# V1_2.net
KiCad netlist of a schematic drawn in Altium Designer
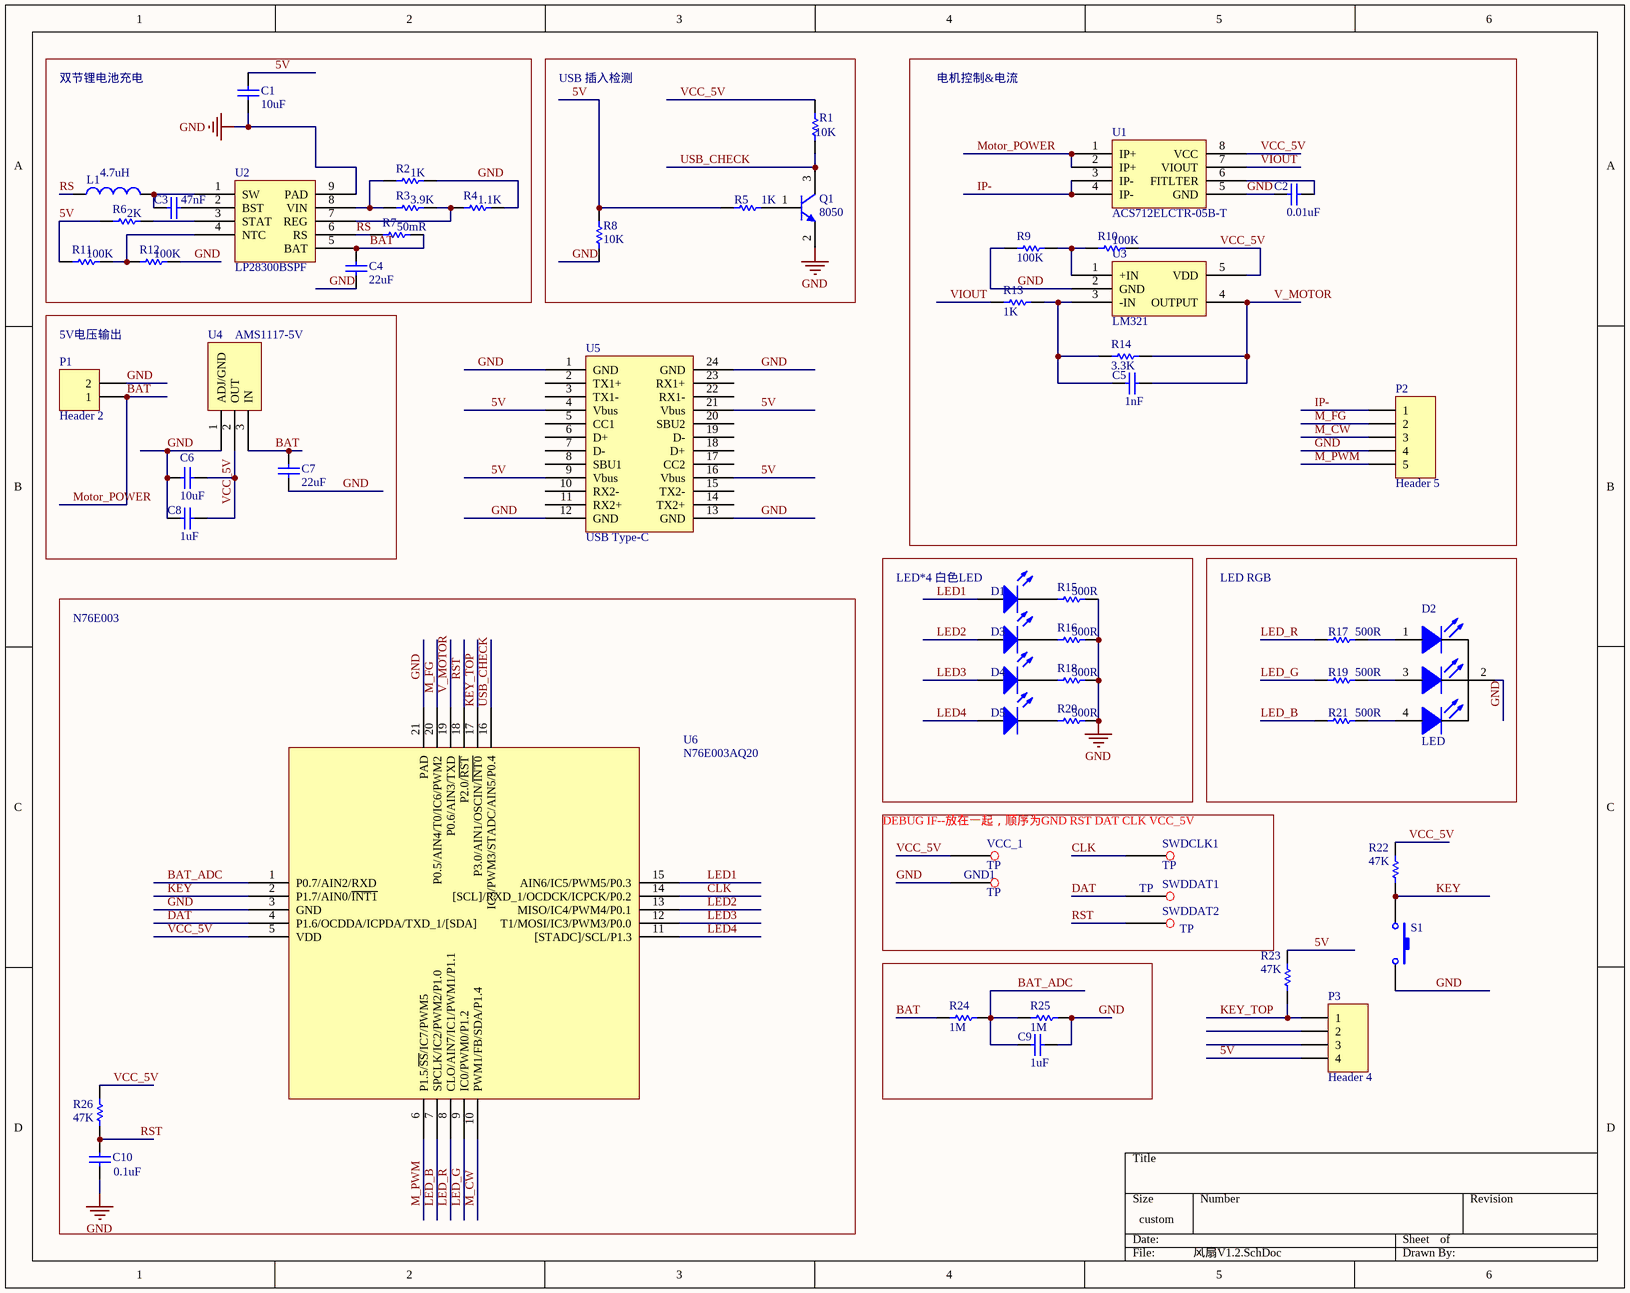
[diagram p0: 风扇V1.2.SchDoc]

(export (version "E")
  (design (tool "Eeschema 10.0.6"))
  (components
    (comp (ref "C1")
      (value "10uF")
      (footprint "c-0402")
      (description "Capacitor")
      (fields (field (name "Comment") "Cap") (field (name "PUBLISHER") "Altium Limited"))
      (libsource (lib "Miscellaneous Devices") (part "Cap"))
    )
    (comp (ref "C2")
      (value "0.01uF")
      (footprint "c-0402")
      (description "Capacitor")
      (fields (field (name "Comment") "Cap") (field (name "PUBLISHER") "Altium Limited"))
      (libsource (lib "Miscellaneous Devices") (part "Cap"))
    )
    (comp (ref "C3")
      (value "47nF")
      (footprint "c-0402")
      (description "Capacitor")
      (fields (field (name "Comment") "Cap") (field (name "PUBLISHER") "Altium Limited"))
      (libsource (lib "Miscellaneous Devices") (part "Cap"))
    )
    (comp (ref "C4")
      (value "22uF")
      (footprint "c-0402")
      (description "Capacitor")
      (fields (field (name "Comment") "Cap") (field (name "PUBLISHER") "Altium Limited"))
      (libsource (lib "Miscellaneous Devices") (part "Cap"))
    )
    (comp (ref "C5")
      (value "1nF")
      (footprint "c-0402")
      (description "Capacitor")
      (fields (field (name "Comment") "Cap") (field (name "PUBLISHER") "Altium Limited"))
      (libsource (lib "Miscellaneous Devices") (part "Cap"))
    )
    (comp (ref "C6")
      (value "10uF")
      (footprint "c-0402")
      (description "Capacitor")
      (fields (field (name "Comment") "Cap") (field (name "PUBLISHER") "Altium Limited"))
      (libsource (lib "Miscellaneous Devices") (part "Cap"))
    )
    (comp (ref "C7")
      (value "22uF")
      (footprint "c-0402")
      (description "Capacitor")
      (fields (field (name "Comment") "Cap") (field (name "PUBLISHER") "Altium Limited"))
      (libsource (lib "Miscellaneous Devices") (part "Cap"))
    )
    (comp (ref "C8")
      (value "1uF")
      (footprint "c-0402")
      (description "Capacitor")
      (fields (field (name "Comment") "Cap") (field (name "PUBLISHER") "Altium Limited"))
      (libsource (lib "Miscellaneous Devices") (part "Cap"))
    )
    (comp (ref "C9")
      (value "1uF")
      (footprint "c-0402")
      (description "Capacitor")
      (fields (field (name "Comment") "Cap") (field (name "PUBLISHER") "Altium Limited"))
      (libsource (lib "Miscellaneous Devices") (part "Cap"))
    )
    (comp (ref "C10")
      (value "0.1uF")
      (footprint "C-0402")
      (description "Capacitor")
      (fields (field (name "PUBLISHER") "Altium Limited"))
      (libsource (lib "Miscellaneous Devices") (part "Cap"))
    )
    (comp (ref "D1")
      (value "LED0")
      (footprint "Model Name")
      (description "Typical INFRARED GaAs LED")
      (fields (field (name "PUBLISHER") "Altium Limited"))
      (libsource (lib "Miscellaneous Devices") (part "LED0"))
    )
    (comp (ref "D2") (value "LED") (libsource (lib "SA2") (part "LED")))
    (comp (ref "D3")
      (value "LED0")
      (footprint "LED-0")
      (description "Typical INFRARED GaAs LED")
      (fields (field (name "PUBLISHER") "Altium Limited"))
      (libsource (lib "Miscellaneous Devices") (part "LED0"))
    )
    (comp (ref "D4")
      (value "LED0")
      (footprint "LED-0")
      (description "Typical INFRARED GaAs LED")
      (fields (field (name "PUBLISHER") "Altium Limited"))
      (libsource (lib "Miscellaneous Devices") (part "LED0"))
    )
    (comp (ref "D5")
      (value "LED0")
      (footprint "LED-0")
      (description "Typical INFRARED GaAs LED")
      (fields (field (name "PUBLISHER") "Altium Limited"))
      (libsource (lib "Miscellaneous Devices") (part "LED0"))
    )
    (comp (ref "GND1") (value "TP") (footprint "TP-1.2") (libsource (lib "Others_IC_SCH_LIB") (part "TP")))
    (comp (ref "L1")
      (value "4.7uH")
      (footprint "INDC1005AL")
      (description "Inductor")
      (fields (field (name "PUBLISHER") "Altium Limited"))
      (libsource (lib "Miscellaneous Devices") (part "Inductor"))
    )
    (comp (ref "P1")
      (value "Header 2")
      (footprint "HDR1X2")
      (description "Header, 2-Pin")
      (fields (field (name "PUBLISHER") "Altium Limited"))
      (libsource (lib "Miscellaneous Connectors") (part "Header 2"))
    )
    (comp (ref "P2")
      (value "Header 5")
      (footprint "HDR1X5")
      (description "Header, 5-Pin")
      (fields (field (name "PUBLISHER") "Altium Limited"))
      (libsource (lib "Miscellaneous Connectors") (part "Header 5"))
    )
    (comp (ref "P3")
      (value "Header 4")
      (footprint "HDR1X4")
      (description "Header, 4-Pin")
      (fields (field (name "PUBLISHER") "Altium Limited"))
      (libsource (lib "Miscellaneous Connectors") (part "Header 4"))
    )
    (comp (ref "Q1")
      (value "8050")
      (footprint "SOT-23")
      (description "NPN Bipolar Transistor")
      (fields (field (name "PUBLISHER") "Altium Limited"))
      (libsource (lib "Miscellaneous Devices") (part "NPN"))
    )
    (comp (ref "R1")
      (value "10K")
      (footprint "R-0402")
      (description "Resistor")
      (fields (field (name "PUBLISHER") "Altium Limited"))
      (libsource (lib "Miscellaneous Devices") (part "Res1"))
    )
    (comp (ref "R2")
      (value "1K")
      (footprint "R-0402")
      (description "Resistor")
      (fields (field (name "Comment") "Res1") (field (name "PUBLISHER") "Altium Limited"))
      (libsource (lib "Miscellaneous Devices") (part "Res1"))
    )
    (comp (ref "R3")
      (value "3.9K")
      (footprint "R-0402")
      (description "Resistor")
      (fields (field (name "Comment") "Res1") (field (name "PUBLISHER") "Altium Limited"))
      (libsource (lib "Miscellaneous Devices") (part "Res1"))
    )
    (comp (ref "R4")
      (value "1.1K")
      (footprint "R-0402")
      (description "Resistor")
      (fields (field (name "Comment") "Res1") (field (name "PUBLISHER") "Altium Limited"))
      (libsource (lib "Miscellaneous Devices") (part "Res1"))
    )
    (comp (ref "R5")
      (value "1K")
      (footprint "R-0402")
      (description "Resistor")
      (fields (field (name "PUBLISHER") "Altium Limited"))
      (libsource (lib "Miscellaneous Devices") (part "Res1"))
    )
    (comp (ref "R6")
      (value "2K")
      (footprint "R-0402")
      (description "Resistor")
      (fields (field (name "Comment") "Res1") (field (name "PUBLISHER") "Altium Limited"))
      (libsource (lib "Miscellaneous Devices") (part "Res1"))
    )
    (comp (ref "R7")
      (value "50mR")
      (footprint "R-0402")
      (description "Resistor")
      (fields (field (name "Comment") "Res1") (field (name "PUBLISHER") "Altium Limited"))
      (libsource (lib "Miscellaneous Devices") (part "Res1"))
    )
    (comp (ref "R8")
      (value "10K")
      (footprint "R-0402")
      (description "Resistor")
      (fields (field (name "Comment") "Res1") (field (name "PUBLISHER") "Altium Limited"))
      (libsource (lib "Miscellaneous Devices") (part "Res1"))
    )
    (comp (ref "R9")
      (value "100K")
      (footprint "R-0402")
      (description "Resistor")
      (fields (field (name "Comment") "Res1") (field (name "PUBLISHER") "Altium Limited"))
      (libsource (lib "Miscellaneous Devices") (part "Res1"))
    )
    (comp (ref "R10")
      (value "100K")
      (footprint "R-0402")
      (description "Resistor")
      (fields (field (name "Comment") "Res1") (field (name "PUBLISHER") "Altium Limited"))
      (libsource (lib "Miscellaneous Devices") (part "Res1"))
    )
    (comp (ref "R11")
      (value "100K")
      (footprint "R-0402")
      (description "Resistor")
      (fields (field (name "Comment") "Res1") (field (name "PUBLISHER") "Altium Limited"))
      (libsource (lib "Miscellaneous Devices") (part "Res1"))
    )
    (comp (ref "R12")
      (value "100K")
      (footprint "R-0402")
      (description "Resistor")
      (fields (field (name "Comment") "Res1") (field (name "PUBLISHER") "Altium Limited"))
      (libsource (lib "Miscellaneous Devices") (part "Res1"))
    )
    (comp (ref "R13")
      (value "1K")
      (footprint "R-0402")
      (description "Resistor")
      (fields (field (name "Comment") "Res1") (field (name "PUBLISHER") "Altium Limited"))
      (libsource (lib "Miscellaneous Devices") (part "Res1"))
    )
    (comp (ref "R14")
      (value "3.3K")
      (footprint "R-0402")
      (description "Resistor")
      (fields (field (name "Comment") "Res1") (field (name "PUBLISHER") "Altium Limited"))
      (libsource (lib "Miscellaneous Devices") (part "Res1"))
    )
    (comp (ref "R15")
      (value "500R")
      (footprint "R-0402")
      (description "Resistor")
      (fields (field (name "Comment") "Res1") (field (name "PUBLISHER") "Altium Limited"))
      (libsource (lib "Miscellaneous Devices") (part "Res1"))
    )
    (comp (ref "R16")
      (value "500R")
      (footprint "R-0402")
      (description "Resistor")
      (fields (field (name "Comment") "Res1") (field (name "PUBLISHER") "Altium Limited"))
      (libsource (lib "Miscellaneous Devices") (part "Res1"))
    )
    (comp (ref "R17")
      (value "500R")
      (footprint "R-0402")
      (description "Resistor")
      (fields (field (name "PUBLISHER") "Altium Limited"))
      (libsource (lib "Miscellaneous Devices") (part "Res1"))
    )
    (comp (ref "R18")
      (value "500R")
      (footprint "R-0402")
      (description "Resistor")
      (fields (field (name "Comment") "Res1") (field (name "PUBLISHER") "Altium Limited"))
      (libsource (lib "Miscellaneous Devices") (part "Res1"))
    )
    (comp (ref "R19")
      (value "500R")
      (footprint "R-0402")
      (description "Resistor")
      (fields (field (name "PUBLISHER") "Altium Limited"))
      (libsource (lib "Miscellaneous Devices") (part "Res1"))
    )
    (comp (ref "R20")
      (value "500R")
      (footprint "R-0402")
      (description "Resistor")
      (fields (field (name "Comment") "Res1") (field (name "PUBLISHER") "Altium Limited"))
      (libsource (lib "Miscellaneous Devices") (part "Res1"))
    )
    (comp (ref "R21")
      (value "500R")
      (footprint "R-0402")
      (description "Resistor")
      (fields (field (name "PUBLISHER") "Altium Limited"))
      (libsource (lib "Miscellaneous Devices") (part "Res1"))
    )
    (comp (ref "R22")
      (value "47K")
      (footprint "r-0201")
      (description "Resistor")
      (fields (field (name "Comment") "Res1") (field (name "PUBLISHER") "Altium Limited"))
      (libsource (lib "Miscellaneous Devices") (part "Res1"))
    )
    (comp (ref "R23")
      (value "47K")
      (footprint "r-0201")
      (description "Resistor")
      (fields (field (name "Comment") "Res1") (field (name "PUBLISHER") "Altium Limited"))
      (libsource (lib "Miscellaneous Devices") (part "Res1"))
    )
    (comp (ref "R24")
      (value "1M")
      (footprint "R-0402")
      (description "Resistor")
      (fields (field (name "Comment") "Res1") (field (name "PUBLISHER") "Altium Limited"))
      (libsource (lib "Miscellaneous Devices") (part "Res1"))
    )
    (comp (ref "R25")
      (value "1M")
      (footprint "R-0402")
      (description "Resistor")
      (fields (field (name "Comment") "Res1") (field (name "PUBLISHER") "Altium Limited"))
      (libsource (lib "Miscellaneous Devices") (part "Res1"))
    )
    (comp (ref "R26")
      (value "47K")
      (footprint "R-0402")
      (description "Resistor")
      (fields (field (name "PUBLISHER") "Altium Limited"))
      (libsource (lib "Miscellaneous Devices") (part "Res1"))
    )
    (comp (ref "S1")
      (value "SW-PB")
      (footprint "SWITCH")
      (description "Switch")
      (fields (field (name "PUBLISHER") "Altium Limited"))
      (libsource (lib "Miscellaneous Devices") (part "SW-PB"))
    )
    (comp (ref "SWDCLK1") (value "TP") (footprint "TP-1.2") (libsource (lib "Others_IC_SCH_LIB") (part "TP")))
    (comp (ref "SWDDAT1") (value "TP") (footprint "TP-1.2") (libsource (lib "Others_IC_SCH_LIB") (part "TP")))
    (comp (ref "SWDDAT2") (value "TP") (footprint "TP-1.2") (libsource (lib "Others_IC_SCH_LIB") (part "TP")))
    (comp (ref "U1")
      (value "ACS712ELCTR-05B-T")
      (footprint "SOIC8")
      (libsource (lib "Others_IC_SCH_LIB") (part "ACS712ELCTR-05B-T"))
    )
    (comp (ref "U2")
      (value "LP28300BSPF")
      (footprint "ESOP8")
      (libsource (lib "Others_IC_SCH_LIB") (part "LP28300BSPF"))
    )
    (comp (ref "U3")
      (value "LM321")
      (footprint "SOT-23-5")
      (libsource (lib "Others_IC_SCH_LIB") (part "LM321"))
    )
    (comp (ref "U4") (value "AMS1117-5V") (libsource (lib "Others_IC_SCH_LIB") (part "AMS1117")))
    (comp (ref "U5") (value "USB Type-C") (libsource (lib "Others_IC_SCH_LIB") (part "USB Type-C")))
    (comp (ref "U6")
      (value "N76E003AQ20")
      (footprint "QFN-20 0.4mm")
      (libsource (lib "Others_IC_SCH_LIB") (part "N76E003AQ20"))
    )
    (comp (ref "VCC_1") (value "TP") (footprint "TP-1.2") (libsource (lib "Others_IC_SCH_LIB") (part "TP")))
  )
  (nets
    (net (code "1") (name "/5V") (class "Default")
      (node (ref "C1") (pin "1") (pinfunction "1_1") (pintype "passive"))
      (node (ref "P3") (pin "4") (pinfunction "4_4") (pintype "passive"))
      (node (ref "R11") (pin "2") (pinfunction "2_2") (pintype "passive"))
      (node (ref "R23") (pin "2") (pinfunction "2_2") (pintype "passive"))
      (node (ref "R5") (pin "1") (pinfunction "1_1") (pintype "passive"))
      (node (ref "R6") (pin "2") (pinfunction "2_2") (pintype "passive"))
      (node (ref "R8") (pin "1") (pinfunction "1_1") (pintype "passive"))
      (node (ref "U5") (pin "16") (pinfunction "Vbus_16") (pintype "passive"))
      (node (ref "U5") (pin "21") (pinfunction "Vbus_21") (pintype "passive"))
      (node (ref "U5") (pin "4") (pinfunction "Vbus_4") (pintype "passive"))
      (node (ref "U5") (pin "9") (pinfunction "Vbus_9") (pintype "passive"))
    )
    (net (code "2") (name "/BAT") (class "Default")
      (node (ref "C4") (pin "1") (pinfunction "1_1") (pintype "passive"))
      (node (ref "C7") (pin "2") (pinfunction "2_2") (pintype "passive"))
      (node (ref "P1") (pin "1") (pinfunction "1_1") (pintype "passive"))
      (node (ref "R24") (pin "1") (pinfunction "1_1") (pintype "passive"))
      (node (ref "R7") (pin "1") (pinfunction "1_1") (pintype "passive"))
      (node (ref "U1") (pin "1") (pinfunction "IP+_1") (pintype "passive"))
      (node (ref "U1") (pin "2") (pinfunction "IP+_2") (pintype "passive"))
      (node (ref "U2") (pin "5") (pinfunction "BAT_5") (pintype "passive"))
      (node (ref "U4") (pin "3") (pinfunction "IN_3") (pintype "passive"))
    )
    (net (code "3") (name "/BAT_ADC") (class "Default")
      (node (ref "C9") (pin "2") (pinfunction "2_2") (pintype "passive"))
      (node (ref "R24") (pin "2") (pinfunction "2_2") (pintype "passive"))
      (node (ref "R25") (pin "1") (pinfunction "1_1") (pintype "passive"))
      (node (ref "U6") (pin "1") (pinfunction "P0.7/AIN2/RXD_1") (pintype "passive"))
    )
    (net (code "4") (name "/CLK") (class "Default")
      (node (ref "SWDCLK1") (pin "1") (pinfunction "1_1") (pintype "passive"))
      (node (ref "U6") (pin "14") (pinfunction "[SCL]/RXD_1/OCDCK/ICPCK/P0.2_14") (pintype "passive"))
    )
    (net (code "5") (name "/DAT") (class "Default")
      (node (ref "SWDDAT1") (pin "1") (pinfunction "1_1") (pintype "passive"))
      (node (ref "U6") (pin "4") (pinfunction "P1.6/OCDDA/ICPDA/TXD_1/[SDA]_4") (pintype "passive"))
    )
    (net (code "6") (name "/IP-") (class "Default")
      (node (ref "P2") (pin "1") (pinfunction "1_1") (pintype "passive"))
      (node (ref "U1") (pin "3") (pinfunction "IP-_3") (pintype "passive"))
      (node (ref "U1") (pin "4") (pinfunction "IP-_4") (pintype "passive"))
    )
    (net (code "7") (name "/KEY") (class "Default")
      (node (ref "R22") (pin "1") (pinfunction "1_1") (pintype "passive"))
      (node (ref "S1") (pin "1") (pinfunction "1_1") (pintype "passive"))
      (node (ref "U6") (pin "2") (pinfunction "P1.7/AIN0/~{INT1}_2") (pintype "passive"))
    )
    (net (code "8") (name "/KEY_TOP") (class "Default")
      (node (ref "P3") (pin "1") (pinfunction "1_1") (pintype "passive"))
      (node (ref "R23") (pin "1") (pinfunction "1_1") (pintype "passive"))
      (node (ref "U6") (pin "17") (pinfunction "P3.0/AIN1/OSCIN/~{INT0}_17") (pintype "passive"))
    )
    (net (code "9") (name "/LED1") (class "Default")
      (node (ref "D1") (pin "1") (pinfunction "A_1") (pintype "passive"))
      (node (ref "U6") (pin "15") (pinfunction "AIN6/IC5/PWM5/P0.3_15") (pintype "passive"))
    )
    (net (code "10") (name "/LED2") (class "Default")
      (node (ref "D3") (pin "1") (pinfunction "A_1") (pintype "passive"))
      (node (ref "U6") (pin "13") (pinfunction "MISO/IC4/PWM4/P0.1_13") (pintype "passive"))
    )
    (net (code "11") (name "/LED3") (class "Default")
      (node (ref "D4") (pin "1") (pinfunction "A_1") (pintype "passive"))
      (node (ref "U6") (pin "12") (pinfunction "T1/MOSI/IC3/PWM3/P0.0_12") (pintype "passive"))
    )
    (net (code "12") (name "/LED4") (class "Default")
      (node (ref "D5") (pin "1") (pinfunction "A_1") (pintype "passive"))
      (node (ref "U6") (pin "11") (pinfunction "[STADC]/SCL/P1.3_11") (pintype "passive"))
    )
    (net (code "13") (name "/LED_B") (class "Default")
      (node (ref "R21") (pin "1") (pinfunction "1_1") (pintype "passive"))
      (node (ref "U6") (pin "7") (pinfunction "SPCLK/IC2/PWM2/P1.0_7") (pintype "passive"))
    )
    (net (code "14") (name "/LED_G") (class "Default")
      (node (ref "R19") (pin "1") (pinfunction "1_1") (pintype "passive"))
      (node (ref "U6") (pin "9") (pinfunction "IC0/PWM0/P1.2_9") (pintype "passive"))
    )
    (net (code "15") (name "/LED_R") (class "Default")
      (node (ref "R17") (pin "1") (pinfunction "1_1") (pintype "passive"))
      (node (ref "U6") (pin "8") (pinfunction "CLO/AIN7/IC1/PWM1/P1.1_8") (pintype "passive"))
    )
    (net (code "16") (name "/M_CW") (class "Default")
      (node (ref "P2") (pin "3") (pinfunction "3_3") (pintype "passive"))
      (node (ref "U6") (pin "10") (pinfunction "PWM1/FB/SDA/P1.4_10") (pintype "passive"))
    )
    (net (code "17") (name "/M_FG") (class "Default")
      (node (ref "P2") (pin "2") (pinfunction "2_2") (pintype "passive"))
      (node (ref "U6") (pin "20") (pinfunction "P0.5/AIN4/T0/IC6/PWM2_20") (pintype "passive"))
    )
    (net (code "18") (name "/M_PWM") (class "Default")
      (node (ref "P2") (pin "5") (pinfunction "5_5") (pintype "passive"))
      (node (ref "U6") (pin "6") (pinfunction "P1.5/~{SS}/IC7/PWM5_6") (pintype "passive"))
    )
    (net (code "19") (name "/RS") (class "Default")
      (node (ref "L1") (pin "1") (pinfunction "1_1") (pintype "passive"))
      (node (ref "R7") (pin "2") (pinfunction "2_2") (pintype "passive"))
      (node (ref "U2") (pin "6") (pinfunction "RS_6") (pintype "passive"))
    )
    (net (code "20") (name "/RST") (class "Default")
      (node (ref "C10") (pin "2") (pinfunction "2_2") (pintype "passive"))
      (node (ref "R26") (pin "1") (pinfunction "1_1") (pintype "passive"))
      (node (ref "SWDDAT2") (pin "1") (pinfunction "1_1") (pintype "passive"))
      (node (ref "U6") (pin "18") (pinfunction "P2.0/~{RST}_18") (pintype "passive"))
    )
    (net (code "21") (name "/USB_CHECK") (class "Default")
      (node (ref "Q1") (pin "3") (pinfunction "C_3") (pintype "passive"))
      (node (ref "R1") (pin "1") (pinfunction "1_1") (pintype "passive"))
      (node (ref "U6") (pin "16") (pinfunction "IC3/PWM3/STADC/AIN5/P0.4_16") (pintype "passive"))
    )
    (net (code "22") (name "/VCC_5V") (class "Default")
      (node (ref "C6") (pin "2") (pinfunction "2_2") (pintype "passive"))
      (node (ref "C8") (pin "2") (pinfunction "2_2") (pintype "passive"))
      (node (ref "R1") (pin "2") (pinfunction "2_2") (pintype "passive"))
      (node (ref "R10") (pin "2") (pinfunction "2_2") (pintype "passive"))
      (node (ref "R22") (pin "2") (pinfunction "2_2") (pintype "passive"))
      (node (ref "R26") (pin "2") (pinfunction "2_2") (pintype "passive"))
      (node (ref "U1") (pin "8") (pinfunction "VCC_8") (pintype "passive"))
      (node (ref "U3") (pin "5") (pinfunction "VDD_5") (pintype "passive"))
      (node (ref "U4") (pin "2") (pinfunction "OUT_2") (pintype "passive"))
      (node (ref "U6") (pin "5") (pinfunction "VDD_5") (pintype "passive"))
      (node (ref "VCC_1") (pin "1") (pinfunction "1_1") (pintype "passive"))
    )
    (net (code "23") (name "/VIOUT") (class "Default")
      (node (ref "R13") (pin "1") (pinfunction "1_1") (pintype "passive"))
      (node (ref "U1") (pin "7") (pinfunction "VIOUT_7") (pintype "passive"))
    )
    (net (code "24") (name "/V_MOTOR") (class "Default")
      (node (ref "C5") (pin "1") (pinfunction "1_1") (pintype "passive"))
      (node (ref "R14") (pin "2") (pinfunction "2_2") (pintype "passive"))
      (node (ref "U3") (pin "4") (pinfunction "OUTPUT_4") (pintype "passive"))
      (node (ref "U6") (pin "19") (pinfunction "P0.6/AIN3/TXD_19") (pintype "passive"))
    )
    (net (code "25") (name "GND") (class "Default")
      (node (ref "C1") (pin "2") (pinfunction "2_2") (pintype "passive"))
      (node (ref "C10") (pin "1") (pinfunction "1_1") (pintype "passive"))
      (node (ref "C2") (pin "2") (pinfunction "2_2") (pintype "passive"))
      (node (ref "C4") (pin "2") (pinfunction "2_2") (pintype "passive"))
      (node (ref "C6") (pin "1") (pinfunction "1_1") (pintype "passive"))
      (node (ref "C7") (pin "1") (pinfunction "1_1") (pintype "passive"))
      (node (ref "C8") (pin "1") (pinfunction "1_1") (pintype "passive"))
      (node (ref "C9") (pin "1") (pinfunction "1_1") (pintype "passive"))
      (node (ref "D2") (pin "2") (pinfunction "2_2") (pintype "passive"))
      (node (ref "GND1") (pin "1") (pinfunction "1_1") (pintype "passive"))
      (node (ref "P1") (pin "2") (pinfunction "2_2") (pintype "passive"))
      (node (ref "P2") (pin "4") (pinfunction "4_4") (pintype "passive"))
      (node (ref "Q1") (pin "2") (pinfunction "E_2") (pintype "passive"))
      (node (ref "R12") (pin "1") (pinfunction "1_1") (pintype "passive"))
      (node (ref "R15") (pin "2") (pinfunction "2_2") (pintype "passive"))
      (node (ref "R16") (pin "2") (pinfunction "2_2") (pintype "passive"))
      (node (ref "R18") (pin "2") (pinfunction "2_2") (pintype "passive"))
      (node (ref "R2") (pin "1") (pinfunction "1_1") (pintype "passive"))
      (node (ref "R20") (pin "2") (pinfunction "2_2") (pintype "passive"))
      (node (ref "R25") (pin "2") (pinfunction "2_2") (pintype "passive"))
      (node (ref "R4") (pin "1") (pinfunction "1_1") (pintype "passive"))
      (node (ref "R8") (pin "2") (pinfunction "2_2") (pintype "passive"))
      (node (ref "R9") (pin "1") (pinfunction "1_1") (pintype "passive"))
      (node (ref "S1") (pin "2") (pinfunction "2_2") (pintype "passive"))
      (node (ref "U1") (pin "5") (pinfunction "GND_5") (pintype "passive"))
      (node (ref "U2") (pin "9") (pinfunction "PAD_9") (pintype "passive"))
      (node (ref "U3") (pin "2") (pinfunction "GND_2") (pintype "passive"))
      (node (ref "U4") (pin "1") (pinfunction "ADJ/GND_1") (pintype "passive"))
      (node (ref "U5") (pin "1") (pinfunction "GND_1") (pintype "passive"))
      (node (ref "U5") (pin "12") (pinfunction "GND_12") (pintype "passive"))
      (node (ref "U5") (pin "13") (pinfunction "GND_13") (pintype "passive"))
      (node (ref "U5") (pin "24") (pinfunction "GND_24") (pintype "passive"))
      (node (ref "U6") (pin "21") (pinfunction "PAD_21") (pintype "passive"))
      (node (ref "U6") (pin "3") (pinfunction "GND_3") (pintype "passive"))
    )
    (net (code "26") (name "Net-(D1-K)") (class "Default")
      (node (ref "D1") (pin "2") (pinfunction "K_2") (pintype "passive"))
      (node (ref "R15") (pin "1") (pinfunction "1_1") (pintype "passive"))
    )
    (net (code "27") (name "Net-(D2-Pad1)") (class "Default")
      (node (ref "D2") (pin "1") (pinfunction "1_1") (pintype "passive"))
      (node (ref "R17") (pin "2") (pinfunction "2_2") (pintype "passive"))
    )
    (net (code "28") (name "Net-(D2-Pad3)") (class "Default")
      (node (ref "D2") (pin "3") (pinfunction "3_3") (pintype "passive"))
      (node (ref "R19") (pin "2") (pinfunction "2_2") (pintype "passive"))
    )
    (net (code "29") (name "Net-(D2-Pad4)") (class "Default")
      (node (ref "D2") (pin "4") (pinfunction "4_4") (pintype "passive"))
      (node (ref "R21") (pin "2") (pinfunction "2_2") (pintype "passive"))
    )
    (net (code "30") (name "Net-(D3-K)") (class "Default")
      (node (ref "D3") (pin "2") (pinfunction "K_2") (pintype "passive"))
      (node (ref "R16") (pin "1") (pinfunction "1_1") (pintype "passive"))
    )
    (net (code "31") (name "Net-(D4-K)") (class "Default")
      (node (ref "D4") (pin "2") (pinfunction "K_2") (pintype "passive"))
      (node (ref "R18") (pin "1") (pinfunction "1_1") (pintype "passive"))
    )
    (net (code "32") (name "Net-(D5-K)") (class "Default")
      (node (ref "D5") (pin "2") (pinfunction "K_2") (pintype "passive"))
      (node (ref "R20") (pin "1") (pinfunction "1_1") (pintype "passive"))
    )
    (net (code "33") (name "Net-(Q1-B)") (class "Default")
      (node (ref "Q1") (pin "1") (pinfunction "B_1") (pintype "passive"))
      (node (ref "R5") (pin "2") (pinfunction "2_2") (pintype "passive"))
    )
    (net (code "34") (name "Net-(U1-FITLTER)") (class "Default")
      (node (ref "C2") (pin "1") (pinfunction "1_1") (pintype "passive"))
      (node (ref "U1") (pin "6") (pinfunction "FITLTER_6") (pintype "passive"))
    )
    (net (code "35") (name "Net-(U2-BST)") (class "Default")
      (node (ref "C3") (pin "2") (pinfunction "2_2") (pintype "passive"))
      (node (ref "U2") (pin "2") (pinfunction "BST_2") (pintype "passive"))
    )
    (net (code "36") (name "Net-(U2-NTC)") (class "Default")
      (node (ref "R11") (pin "1") (pinfunction "1_1") (pintype "passive"))
      (node (ref "R12") (pin "2") (pinfunction "2_2") (pintype "passive"))
      (node (ref "U2") (pin "4") (pinfunction "NTC_4") (pintype "passive"))
    )
    (net (code "37") (name "Net-(U2-REG)") (class "Default")
      (node (ref "R3") (pin "1") (pinfunction "1_1") (pintype "passive"))
      (node (ref "R4") (pin "2") (pinfunction "2_2") (pintype "passive"))
      (node (ref "U2") (pin "7") (pinfunction "REG_7") (pintype "passive"))
    )
    (net (code "38") (name "Net-(U2-STAT)") (class "Default")
      (node (ref "R6") (pin "1") (pinfunction "1_1") (pintype "passive"))
      (node (ref "U2") (pin "3") (pinfunction "STAT_3") (pintype "passive"))
    )
    (net (code "39") (name "Net-(U2-SW)") (class "Default")
      (node (ref "C3") (pin "1") (pinfunction "1_1") (pintype "passive"))
      (node (ref "L1") (pin "2") (pinfunction "2_2") (pintype "passive"))
      (node (ref "U2") (pin "1") (pinfunction "SW_1") (pintype "passive"))
    )
    (net (code "40") (name "Net-(U2-VIN)") (class "Default")
      (node (ref "R2") (pin "2") (pinfunction "2_2") (pintype "passive"))
      (node (ref "R3") (pin "2") (pinfunction "2_2") (pintype "passive"))
      (node (ref "U2") (pin "8") (pinfunction "VIN_8") (pintype "passive"))
    )
    (net (code "41") (name "Net-(U3-+IN)") (class "Default")
      (node (ref "R10") (pin "1") (pinfunction "1_1") (pintype "passive"))
      (node (ref "R9") (pin "2") (pinfunction "2_2") (pintype "passive"))
      (node (ref "U3") (pin "1") (pinfunction "+IN_1") (pintype "passive"))
    )
    (net (code "42") (name "Net-(U3--IN)") (class "Default")
      (node (ref "C5") (pin "2") (pinfunction "2_2") (pintype "passive"))
      (node (ref "R13") (pin "2") (pinfunction "2_2") (pintype "passive"))
      (node (ref "R14") (pin "1") (pinfunction "1_1") (pintype "passive"))
      (node (ref "U3") (pin "3") (pinfunction "-IN_3") (pintype "passive"))
    )
    (net (code "43") (name "unconnected-(P3-Pad2)") (class "Default")
      (node (ref "P3") (pin "2") (pinfunction "2_2") (pintype "passive"))
    )
    (net (code "44") (name "unconnected-(P3-Pad3)") (class "Default")
      (node (ref "P3") (pin "3") (pinfunction "3_3") (pintype "passive"))
    )
    (net (code "45") (name "unconnected-(U5-CC1-Pad5)") (class "Default")
      (node (ref "U5") (pin "5") (pinfunction "CC1_5") (pintype "passive"))
    )
    (net (code "46") (name "unconnected-(U5-CC2-Pad17)") (class "Default")
      (node (ref "U5") (pin "17") (pinfunction "CC2_17") (pintype "passive"))
    )
    (net (code "47") (name "unconnected-(U5-D+-Pad6)") (class "Default")
      (node (ref "U5") (pin "6") (pinfunction "D+_6") (pintype "passive"))
    )
    (net (code "48") (name "unconnected-(U5-D+-Pad18)") (class "Default")
      (node (ref "U5") (pin "18") (pinfunction "D+_18") (pintype "passive"))
    )
    (net (code "49") (name "unconnected-(U5-D--Pad7)") (class "Default")
      (node (ref "U5") (pin "7") (pinfunction "D-_7") (pintype "passive"))
    )
    (net (code "50") (name "unconnected-(U5-D--Pad19)") (class "Default")
      (node (ref "U5") (pin "19") (pinfunction "D-_19") (pintype "passive"))
    )
    (net (code "51") (name "unconnected-(U5-RX1+-Pad23)") (class "Default")
      (node (ref "U5") (pin "23") (pinfunction "RX1+_23") (pintype "passive"))
    )
    (net (code "52") (name "unconnected-(U5-RX1--Pad22)") (class "Default")
      (node (ref "U5") (pin "22") (pinfunction "RX1-_22") (pintype "passive"))
    )
    (net (code "53") (name "unconnected-(U5-RX2+-Pad11)") (class "Default")
      (node (ref "U5") (pin "11") (pinfunction "RX2+_11") (pintype "passive"))
    )
    (net (code "54") (name "unconnected-(U5-RX2--Pad10)") (class "Default")
      (node (ref "U5") (pin "10") (pinfunction "RX2-_10") (pintype "passive"))
    )
    (net (code "55") (name "unconnected-(U5-SBU1-Pad8)") (class "Default")
      (node (ref "U5") (pin "8") (pinfunction "SBU1_8") (pintype "passive"))
    )
    (net (code "56") (name "unconnected-(U5-SBU2-Pad20)") (class "Default")
      (node (ref "U5") (pin "20") (pinfunction "SBU2_20") (pintype "passive"))
    )
    (net (code "57") (name "unconnected-(U5-TX1+-Pad2)") (class "Default")
      (node (ref "U5") (pin "2") (pinfunction "TX1+_2") (pintype "passive"))
    )
    (net (code "58") (name "unconnected-(U5-TX1--Pad3)") (class "Default")
      (node (ref "U5") (pin "3") (pinfunction "TX1-_3") (pintype "passive"))
    )
    (net (code "59") (name "unconnected-(U5-TX2+-Pad14)") (class "Default")
      (node (ref "U5") (pin "14") (pinfunction "TX2+_14") (pintype "passive"))
    )
    (net (code "60") (name "unconnected-(U5-TX2--Pad15)") (class "Default")
      (node (ref "U5") (pin "15") (pinfunction "TX2-_15") (pintype "passive"))
    )
  )
)
